# ESP-WROOM02-Breakout_v11.net
KiCad netlist of a schematic drawn in EAGLE
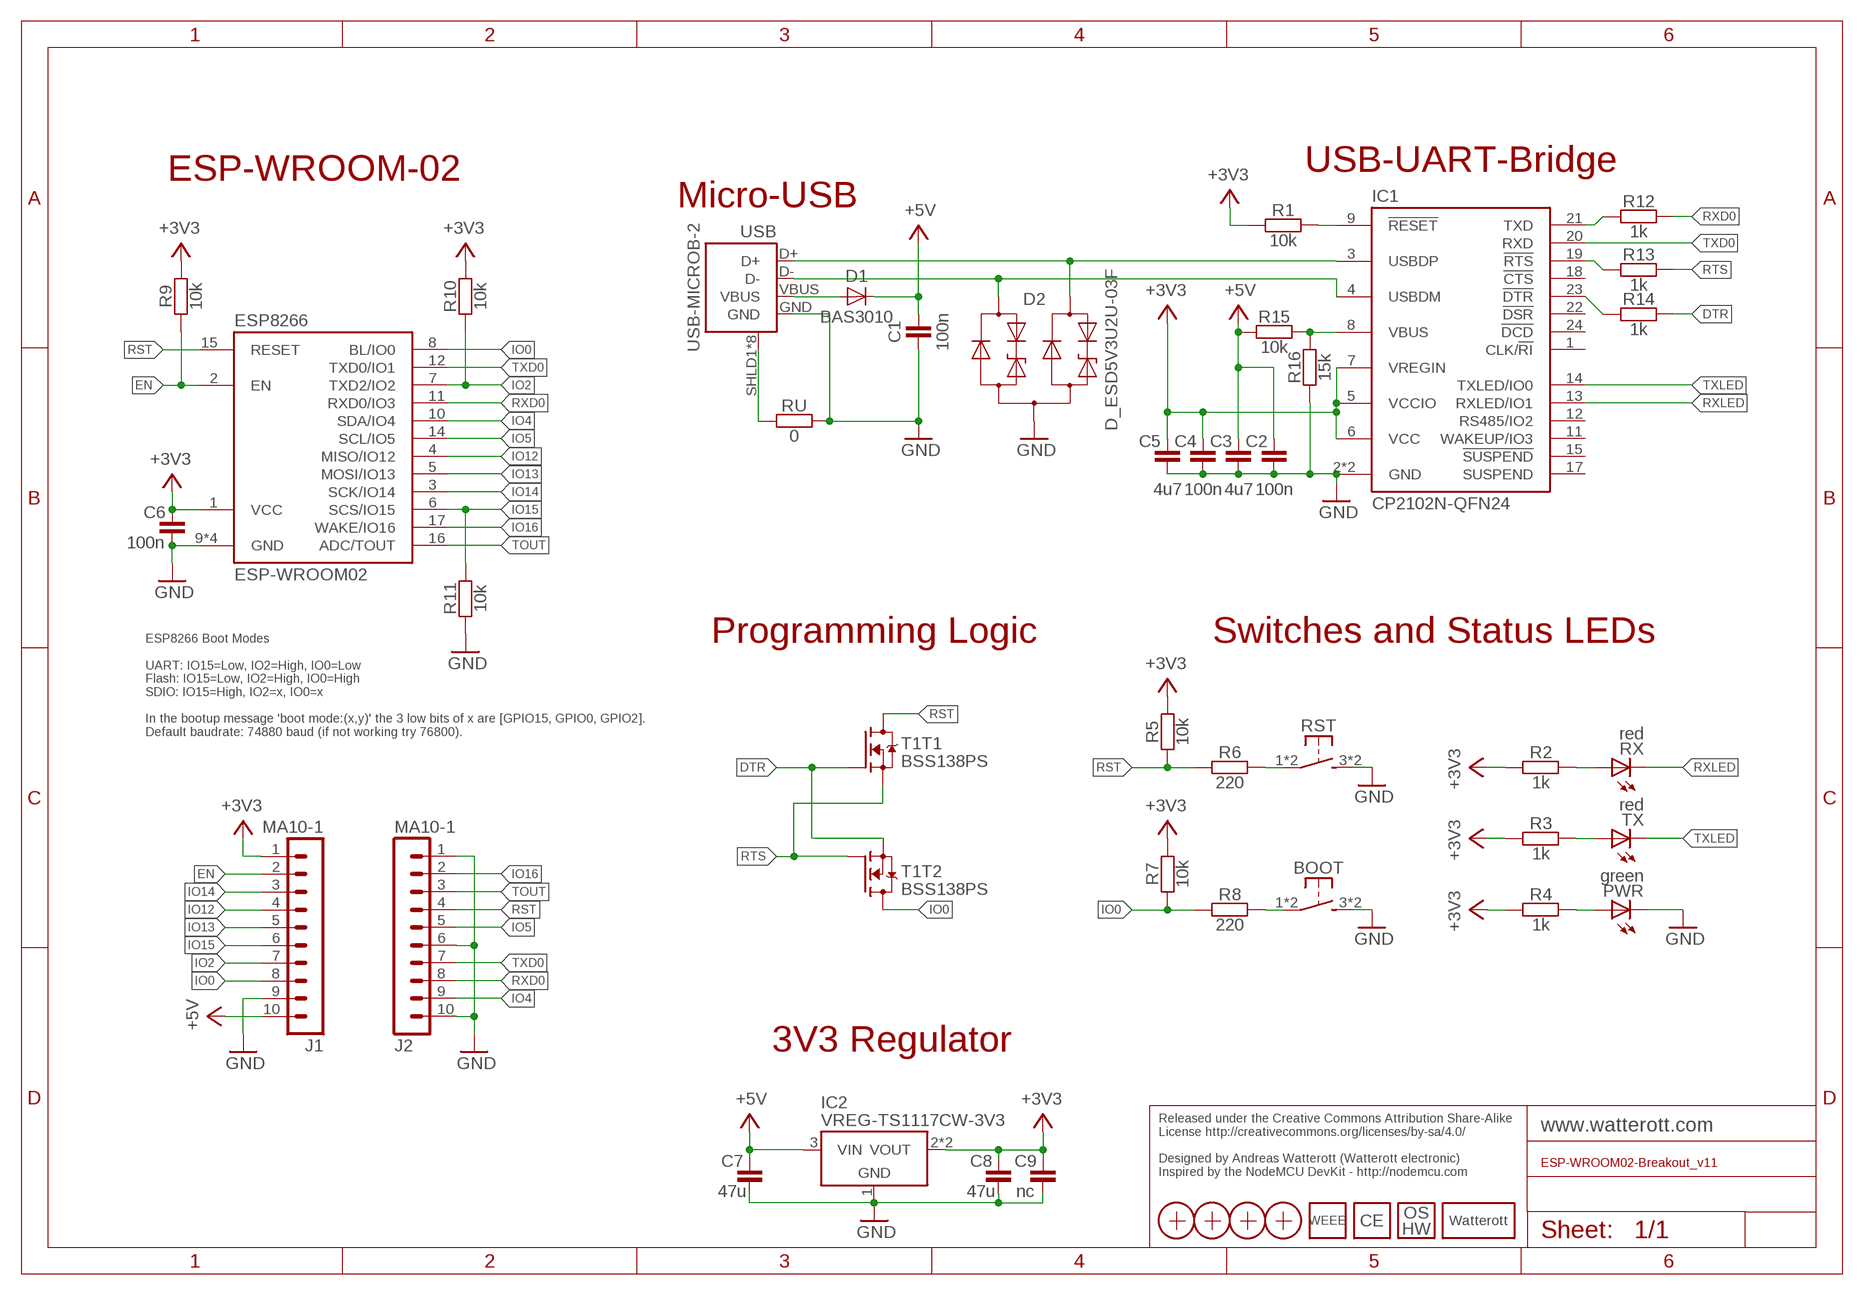
[diagram p0: schematic, sheet 1]

(export (version "E")
  (design (tool "Eeschema 10.0.6"))
  (components
    (comp (ref "BOOT")
      (value "SW-TACTILE-PTS840P")
      (footprint "eagle-import:PTS840P")
      (libsource (lib "eagle-import") (part "SW-TACTILE-PTS840P"))
    )
    (comp (ref "C1")
      (value "100n")
      (footprint "eagle-import:C0402")
      (libsource (lib "eagle-import") (part "CAPACITOR-0402"))
    )
    (comp (ref "C2")
      (value "100n")
      (footprint "eagle-import:C0402")
      (libsource (lib "eagle-import") (part "CAPACITOR-0402"))
    )
    (comp (ref "C3")
      (value "4u7")
      (footprint "eagle-import:C0603")
      (libsource (lib "eagle-import") (part "CAPACITOR-0603"))
    )
    (comp (ref "C4")
      (value "100n")
      (footprint "eagle-import:C0402")
      (libsource (lib "eagle-import") (part "CAPACITOR-0402"))
    )
    (comp (ref "C5")
      (value "4u7")
      (footprint "eagle-import:C0603")
      (libsource (lib "eagle-import") (part "CAPACITOR-0603"))
    )
    (comp (ref "C6")
      (value "100n")
      (footprint "eagle-import:C0402")
      (libsource (lib "eagle-import") (part "CAPACITOR-0402"))
    )
    (comp (ref "C7")
      (value "47u")
      (footprint "eagle-import:C1206")
      (libsource (lib "eagle-import") (part "CAPACITOR-1206"))
    )
    (comp (ref "C8")
      (value "47u")
      (footprint "eagle-import:C1206")
      (libsource (lib "eagle-import") (part "CAPACITOR-1206"))
    )
    (comp (ref "C9")
      (value "nc")
      (footprint "eagle-import:C1206")
      (libsource (lib "eagle-import") (part "CAPACITOR-1206"))
    )
    (comp (ref "D1")
      (value "BAS3010")
      (footprint "eagle-import:SOD323")
      (libsource (lib "eagle-import") (part "DIODE-SOD323"))
    )
    (comp (ref "D2")
      (value "D_ESD5V3U2U-03F")
      (footprint "eagle-import:SOT723")
      (libsource (lib "eagle-import") (part "D_ESD5V3U2U-03F"))
    )
    (comp (ref "ESP8266")
      (value "ESP-WROOM02")
      (footprint "eagle-import:ESP-WROOM02")
      (libsource (lib "eagle-import") (part "ESP-WROOM02"))
    )
    (comp (ref "IC1")
      (value "CP2102N-QFN24")
      (footprint "eagle-import:QFN24-PAD")
      (libsource (lib "eagle-import") (part "CP2102N-QFN24"))
    )
    (comp (ref "IC2")
      (value "VREG-TS1117CW-3V3")
      (footprint "eagle-import:SOT223")
      (libsource (lib "eagle-import") (part "VREG-TS1117CW-3V3"))
    )
    (comp (ref "J1")
      (value "MA10-1")
      (footprint "eagle-import:MA10-1")
      (libsource (lib "eagle-import") (part "MA10-1"))
    )
    (comp (ref "J2")
      (value "MA10-1")
      (footprint "eagle-import:MA10-1")
      (libsource (lib "eagle-import") (part "MA10-1"))
    )
    (comp (ref "LOGO1")
      (value "LOGO_SPARK-4")
      (footprint "eagle-import:SPARK_4MM")
      (libsource (lib "eagle-import") (part "LOGO_SPARK-4"))
    )
    (comp (ref "LOGO2")
      (value "LOGO_OSHW-2")
      (footprint "eagle-import:OSHW_2MM")
      (libsource (lib "eagle-import") (part "LOGO_OSHW-2"))
    )
    (comp (ref "LOGO3")
      (value "LOGO_WEEE-4")
      (footprint "eagle-import:WEEE_4MM")
      (libsource (lib "eagle-import") (part "LOGO_WEEE-4"))
    )
    (comp (ref "LOGO4")
      (value "LOGO_CE-2")
      (footprint "eagle-import:CE_2MM")
      (libsource (lib "eagle-import") (part "LOGO_CE-2"))
    )
    (comp (ref "PWR")
      (value "green")
      (footprint "eagle-import:C0603")
      (libsource (lib "eagle-import") (part "LED-0603"))
    )
    (comp (ref "R1")
      (value "10k")
      (footprint "eagle-import:C0402")
      (libsource (lib "eagle-import") (part "RESISTOR-0402"))
    )
    (comp (ref "R2")
      (value "1k")
      (footprint "eagle-import:C0402")
      (libsource (lib "eagle-import") (part "RESISTOR-0402"))
    )
    (comp (ref "R3")
      (value "1k")
      (footprint "eagle-import:C0402")
      (libsource (lib "eagle-import") (part "RESISTOR-0402"))
    )
    (comp (ref "R4")
      (value "1k")
      (footprint "eagle-import:C0402")
      (libsource (lib "eagle-import") (part "RESISTOR-0402"))
    )
    (comp (ref "R5")
      (value "10k")
      (footprint "eagle-import:C0402")
      (libsource (lib "eagle-import") (part "RESISTOR-0402"))
    )
    (comp (ref "R6")
      (value "220")
      (footprint "eagle-import:C0402")
      (libsource (lib "eagle-import") (part "RESISTOR-0402"))
    )
    (comp (ref "R7")
      (value "10k")
      (footprint "eagle-import:C0402")
      (libsource (lib "eagle-import") (part "RESISTOR-0402"))
    )
    (comp (ref "R8")
      (value "220")
      (footprint "eagle-import:C0402")
      (libsource (lib "eagle-import") (part "RESISTOR-0402"))
    )
    (comp (ref "R9")
      (value "10k")
      (footprint "eagle-import:C0402")
      (libsource (lib "eagle-import") (part "RESISTOR-0402"))
    )
    (comp (ref "R10")
      (value "10k")
      (footprint "eagle-import:C0402")
      (libsource (lib "eagle-import") (part "RESISTOR-0402"))
    )
    (comp (ref "R11")
      (value "10k")
      (footprint "eagle-import:C0402")
      (libsource (lib "eagle-import") (part "RESISTOR-0402"))
    )
    (comp (ref "R12")
      (value "1k")
      (footprint "eagle-import:C0402")
      (libsource (lib "eagle-import") (part "RESISTOR-0402"))
    )
    (comp (ref "R13")
      (value "1k")
      (footprint "eagle-import:C0402")
      (libsource (lib "eagle-import") (part "RESISTOR-0402"))
    )
    (comp (ref "R14")
      (value "1k")
      (footprint "eagle-import:C0402")
      (libsource (lib "eagle-import") (part "RESISTOR-0402"))
    )
    (comp (ref "R15")
      (value "10k")
      (footprint "eagle-import:C0402")
      (libsource (lib "eagle-import") (part "RESISTOR-0402"))
    )
    (comp (ref "R16")
      (value "15k")
      (footprint "eagle-import:C0402")
      (libsource (lib "eagle-import") (part "RESISTOR-0402"))
    )
    (comp (ref "RST")
      (value "SW-TACTILE-PTS840P")
      (footprint "eagle-import:PTS840P")
      (libsource (lib "eagle-import") (part "SW-TACTILE-PTS840P"))
    )
    (comp (ref "RU")
      (value "0")
      (footprint "eagle-import:C0402")
      (libsource (lib "eagle-import") (part "RESISTOR-0402"))
    )
    (comp (ref "RX")
      (value "red")
      (footprint "eagle-import:C0603")
      (libsource (lib "eagle-import") (part "LED-0603"))
    )
    (comp (ref "T1")
      (value "BSS138PS")
      (footprint "eagle-import:SOT363")
      (libsource (lib "eagle-import") (part "BSS138PS"))
    )
    (comp (ref "TX")
      (value "red")
      (footprint "eagle-import:C0603")
      (libsource (lib "eagle-import") (part "LED-0603"))
    )
    (comp (ref "USB")
      (value "USB-MICROB-2")
      (footprint "eagle-import:USB-MICROB-10118194")
      (libsource (lib "eagle-import") (part "USB-MICROB-2"))
    )
    (comp (ref "X1")
      (value "PASSER-07")
      (footprint "eagle-import:PASSER_07MM")
      (libsource (lib "eagle-import") (part "PASSER-07"))
    )
    (comp (ref "X2")
      (value "PASSER-07")
      (footprint "eagle-import:PASSER_07MM")
      (libsource (lib "eagle-import") (part "PASSER-07"))
    )
    (comp (ref "X3")
      (value "PASSER-07")
      (footprint "eagle-import:PASSER_07MM")
      (libsource (lib "eagle-import") (part "PASSER-07"))
    )
    (comp (ref "X4")
      (value "PASSER-07")
      (footprint "eagle-import:PASSER_07MM")
      (libsource (lib "eagle-import") (part "PASSER-07"))
    )
  )
  (nets
    (net (code "1") (name "+3V3") (class "Default")
      (node (ref "C4") (pin "2") (pinfunction "2_2") (pintype "passive"))
      (node (ref "C5") (pin "2") (pinfunction "2_2") (pintype "passive"))
      (node (ref "C6") (pin "2") (pinfunction "2_2") (pintype "passive"))
      (node (ref "C8") (pin "2") (pinfunction "2_2") (pintype "passive"))
      (node (ref "C9") (pin "2") (pinfunction "2_2") (pintype "passive"))
      (node (ref "ESP8266") (pin "1") (pinfunction "VCC_1") (pintype "power_in"))
      (node (ref "IC1") (pin "5") (pinfunction "VCCIO_5") (pintype "power_in"))
      (node (ref "IC1") (pin "6") (pinfunction "VCC_6") (pintype "power_in"))
      (node (ref "IC1") (pin "7") (pinfunction "VREGIN_7") (pintype "power_in"))
      (node (ref "IC2") (pin "2") (pinfunction "VOUT_2") (pintype "power_in"))
      (node (ref "IC2") (pin "4") (pinfunction "VOUT_4") (pintype "power_in"))
      (node (ref "J1") (pin "1") (pinfunction "1_1") (pintype "passive"))
      (node (ref "R1") (pin "1") (pinfunction "1_1") (pintype "passive"))
      (node (ref "R10") (pin "2") (pinfunction "2_2") (pintype "passive"))
      (node (ref "R2") (pin "1") (pinfunction "1_1") (pintype "passive"))
      (node (ref "R3") (pin "1") (pinfunction "1_1") (pintype "passive"))
      (node (ref "R4") (pin "1") (pinfunction "1_1") (pintype "passive"))
      (node (ref "R5") (pin "2") (pinfunction "2_2") (pintype "passive"))
      (node (ref "R7") (pin "2") (pinfunction "2_2") (pintype "passive"))
      (node (ref "R9") (pin "2") (pinfunction "2_2") (pintype "passive"))
    )
    (net (code "2") (name "+5V") (class "Default")
      (node (ref "C1") (pin "2") (pinfunction "2_2") (pintype "passive"))
      (node (ref "C2") (pin "2") (pinfunction "2_2") (pintype "passive"))
      (node (ref "C3") (pin "2") (pinfunction "2_2") (pintype "passive"))
      (node (ref "C7") (pin "2") (pinfunction "2_2") (pintype "passive"))
      (node (ref "D1") (pin "C") (pinfunction "C_C") (pintype "passive"))
      (node (ref "IC2") (pin "3") (pinfunction "VIN_3") (pintype "power_in"))
      (node (ref "J1") (pin "10") (pinfunction "10_10") (pintype "passive"))
      (node (ref "R15") (pin "1") (pinfunction "1_1") (pintype "passive"))
    )
    (net (code "3") (name "DTR") (class "Default")
      (node (ref "R14") (pin "2") (pinfunction "2_2") (pintype "passive"))
      (node (ref "T1") (pin "2") (pinfunction "G_2") (pintype "passive"))
      (node (ref "T1") (pin "4") (pinfunction "S_4") (pintype "passive"))
    )
    (net (code "4") (name "EN") (class "Default")
      (node (ref "ESP8266") (pin "2") (pinfunction "EN_2") (pintype "bidirectional"))
      (node (ref "J1") (pin "2") (pinfunction "2_2") (pintype "passive"))
      (node (ref "R9") (pin "1") (pinfunction "1_1") (pintype "passive"))
    )
    (net (code "5") (name "GND") (class "Default")
      (node (ref "BOOT") (pin "3") (pinfunction "S1_3") (pintype "passive"))
      (node (ref "BOOT") (pin "4") (pinfunction "S1_4") (pintype "passive"))
      (node (ref "C1") (pin "1") (pinfunction "1_1") (pintype "passive"))
      (node (ref "C2") (pin "1") (pinfunction "1_1") (pintype "passive"))
      (node (ref "C3") (pin "1") (pinfunction "1_1") (pintype "passive"))
      (node (ref "C4") (pin "1") (pinfunction "1_1") (pintype "passive"))
      (node (ref "C5") (pin "1") (pinfunction "1_1") (pintype "passive"))
      (node (ref "C6") (pin "1") (pinfunction "1_1") (pintype "passive"))
      (node (ref "C7") (pin "1") (pinfunction "1_1") (pintype "passive"))
      (node (ref "C8") (pin "1") (pinfunction "1_1") (pintype "passive"))
      (node (ref "C9") (pin "1") (pinfunction "1_1") (pintype "passive"))
      (node (ref "D2") (pin "3") (pinfunction "A_3") (pintype "passive"))
      (node (ref "ESP8266") (pin "13") (pinfunction "GND_13") (pintype "power_in"))
      (node (ref "ESP8266") (pin "18") (pinfunction "GND_18") (pintype "power_in"))
      (node (ref "ESP8266") (pin "9") (pinfunction "GND_9") (pintype "power_in"))
      (node (ref "ESP8266") (pin "TP") (pinfunction "GND_TP") (pintype "power_in"))
      (node (ref "IC1") (pin "2") (pinfunction "GND_2") (pintype "power_in"))
      (node (ref "IC1") (pin "TP") (pinfunction "GND_TP") (pintype "power_in"))
      (node (ref "IC2") (pin "1") (pinfunction "GND_1") (pintype "power_in"))
      (node (ref "J1") (pin "9") (pinfunction "9_9") (pintype "passive"))
      (node (ref "J2") (pin "1") (pinfunction "1_1") (pintype "passive"))
      (node (ref "J2") (pin "10") (pinfunction "10_10") (pintype "passive"))
      (node (ref "J2") (pin "6") (pinfunction "6_6") (pintype "passive"))
      (node (ref "PWR") (pin "C") (pinfunction "C_C") (pintype "passive"))
      (node (ref "R11") (pin "1") (pinfunction "1_1") (pintype "passive"))
      (node (ref "R16") (pin "1") (pinfunction "1_1") (pintype "passive"))
      (node (ref "RST") (pin "3") (pinfunction "S1_3") (pintype "passive"))
      (node (ref "RST") (pin "4") (pinfunction "S1_4") (pintype "passive"))
      (node (ref "RU") (pin "2") (pinfunction "2_2") (pintype "passive"))
      (node (ref "USB") (pin "GND") (pinfunction "GND_GND") (pintype "power_in"))
    )
    (net (code "6") (name "IO0") (class "Default")
      (node (ref "ESP8266") (pin "8") (pinfunction "BL/IO0_8") (pintype "bidirectional"))
      (node (ref "J1") (pin "8") (pinfunction "8_8") (pintype "passive"))
      (node (ref "R7") (pin "1") (pinfunction "1_1") (pintype "passive"))
      (node (ref "R8") (pin "1") (pinfunction "1_1") (pintype "passive"))
      (node (ref "T1") (pin "3") (pinfunction "D_3") (pintype "passive"))
    )
    (net (code "7") (name "IO2") (class "Default")
      (node (ref "ESP8266") (pin "7") (pinfunction "TXD2/IO2_7") (pintype "bidirectional"))
      (node (ref "J1") (pin "7") (pinfunction "7_7") (pintype "passive"))
      (node (ref "R10") (pin "1") (pinfunction "1_1") (pintype "passive"))
    )
    (net (code "8") (name "IO4") (class "Default")
      (node (ref "ESP8266") (pin "10") (pinfunction "SDA/IO4_10") (pintype "bidirectional"))
      (node (ref "J2") (pin "9") (pinfunction "9_9") (pintype "passive"))
    )
    (net (code "9") (name "IO5") (class "Default")
      (node (ref "ESP8266") (pin "14") (pinfunction "SCL/IO5_14") (pintype "bidirectional"))
      (node (ref "J2") (pin "5") (pinfunction "5_5") (pintype "passive"))
    )
    (net (code "10") (name "IO12") (class "Default")
      (node (ref "ESP8266") (pin "4") (pinfunction "MISO/IO12_4") (pintype "bidirectional"))
      (node (ref "J1") (pin "4") (pinfunction "4_4") (pintype "passive"))
    )
    (net (code "11") (name "IO13") (class "Default")
      (node (ref "ESP8266") (pin "5") (pinfunction "MOSI/IO13_5") (pintype "bidirectional"))
      (node (ref "J1") (pin "5") (pinfunction "5_5") (pintype "passive"))
    )
    (net (code "12") (name "IO14") (class "Default")
      (node (ref "ESP8266") (pin "3") (pinfunction "SCK/IO14_3") (pintype "bidirectional"))
      (node (ref "J1") (pin "3") (pinfunction "3_3") (pintype "passive"))
    )
    (net (code "13") (name "IO15") (class "Default")
      (node (ref "ESP8266") (pin "6") (pinfunction "SCS/IO15_6") (pintype "bidirectional"))
      (node (ref "J1") (pin "6") (pinfunction "6_6") (pintype "passive"))
      (node (ref "R11") (pin "2") (pinfunction "2_2") (pintype "passive"))
    )
    (net (code "14") (name "IO16") (class "Default")
      (node (ref "ESP8266") (pin "17") (pinfunction "WAKE/IO16_17") (pintype "bidirectional"))
      (node (ref "J2") (pin "2") (pinfunction "2_2") (pintype "passive"))
    )
    (net (code "15") (name "Net-(BOOT-P1-Pad1)") (class "Default")
      (node (ref "BOOT") (pin "1") (pinfunction "P1_1") (pintype "passive"))
      (node (ref "BOOT") (pin "2") (pinfunction "P1_2") (pintype "passive"))
      (node (ref "R8") (pin "2") (pinfunction "2_2") (pintype "passive"))
    )
    (net (code "16") (name "Net-(D1-PadA)") (class "Default")
      (node (ref "D1") (pin "A") (pinfunction "A_A") (pintype "passive"))
      (node (ref "USB") (pin "VBUS") (pinfunction "VBUS_VBUS") (pintype "power_in"))
    )
    (net (code "17") (name "Net-(D2-C1)") (class "Default")
      (node (ref "D2") (pin "1") (pinfunction "C1_1") (pintype "passive"))
      (node (ref "IC1") (pin "4") (pinfunction "USBDM_4") (pintype "bidirectional"))
      (node (ref "USB") (pin "D-") (pinfunction "D-_D-") (pintype "bidirectional"))
    )
    (net (code "18") (name "Net-(D2-C2)") (class "Default")
      (node (ref "D2") (pin "2") (pinfunction "C2_2") (pintype "passive"))
      (node (ref "IC1") (pin "3") (pinfunction "USBDP_3") (pintype "bidirectional"))
      (node (ref "USB") (pin "D+") (pinfunction "D+_D+") (pintype "bidirectional"))
    )
    (net (code "19") (name "Net-(IC1-TXD)") (class "Default")
      (node (ref "IC1") (pin "21") (pinfunction "TXD_21") (pintype "bidirectional"))
      (node (ref "R12") (pin "1") (pinfunction "1_1") (pintype "passive"))
    )
    (net (code "20") (name "Net-(IC1-VBUS)") (class "Default")
      (node (ref "IC1") (pin "8") (pinfunction "VBUS_8") (pintype "power_in"))
      (node (ref "R15") (pin "2") (pinfunction "2_2") (pintype "passive"))
      (node (ref "R16") (pin "2") (pinfunction "2_2") (pintype "passive"))
    )
    (net (code "21") (name "Net-(IC1-~{DTR})") (class "Default")
      (node (ref "IC1") (pin "23") (pinfunction "~{DTR}_23") (pintype "bidirectional"))
      (node (ref "R14") (pin "1") (pinfunction "1_1") (pintype "passive"))
    )
    (net (code "22") (name "Net-(IC1-~{RESET})") (class "Default")
      (node (ref "IC1") (pin "9") (pinfunction "~{RESET}_9") (pintype "bidirectional"))
      (node (ref "R1") (pin "2") (pinfunction "2_2") (pintype "passive"))
    )
    (net (code "23") (name "Net-(IC1-~{RTS})") (class "Default")
      (node (ref "IC1") (pin "19") (pinfunction "~{RTS}_19") (pintype "bidirectional"))
      (node (ref "R13") (pin "1") (pinfunction "1_1") (pintype "passive"))
    )
    (net (code "24") (name "Net-(PWR-PadA)") (class "Default")
      (node (ref "PWR") (pin "A") (pinfunction "A_A") (pintype "passive"))
      (node (ref "R4") (pin "2") (pinfunction "2_2") (pintype "passive"))
    )
    (net (code "25") (name "Net-(R2-Pad2)") (class "Default")
      (node (ref "R2") (pin "2") (pinfunction "2_2") (pintype "passive"))
      (node (ref "RX") (pin "A") (pinfunction "A_A") (pintype "passive"))
    )
    (net (code "26") (name "Net-(R3-Pad2)") (class "Default")
      (node (ref "R3") (pin "2") (pinfunction "2_2") (pintype "passive"))
      (node (ref "TX") (pin "A") (pinfunction "A_A") (pintype "passive"))
    )
    (net (code "27") (name "Net-(R6-Pad2)") (class "Default")
      (node (ref "R6") (pin "2") (pinfunction "2_2") (pintype "passive"))
      (node (ref "RST") (pin "1") (pinfunction "P1_1") (pintype "passive"))
      (node (ref "RST") (pin "2") (pinfunction "P1_2") (pintype "passive"))
    )
    (net (code "28") (name "Net-(RU-Pad1)") (class "Default")
      (node (ref "RU") (pin "1") (pinfunction "1_1") (pintype "passive"))
      (node (ref "USB") (pin "SHLD1") (pinfunction "SHIELD_SHLD1") (pintype "passive"))
      (node (ref "USB") (pin "SHLD2") (pinfunction "SHIELD_SHLD2") (pintype "passive"))
      (node (ref "USB") (pin "SHLD3") (pinfunction "SHIELD_SHLD3") (pintype "passive"))
      (node (ref "USB") (pin "SHLD4") (pinfunction "SHIELD_SHLD4") (pintype "passive"))
      (node (ref "USB") (pin "SHLD5") (pinfunction "SHIELD_SHLD5") (pintype "passive"))
      (node (ref "USB") (pin "SHLD6") (pinfunction "SHIELD_SHLD6") (pintype "passive"))
      (node (ref "USB") (pin "SHLD7") (pinfunction "SHIELD_SHLD7") (pintype "passive"))
      (node (ref "USB") (pin "SHLD8") (pinfunction "SHIELD_SHLD8") (pintype "passive"))
    )
    (net (code "29") (name "RST") (class "Default")
      (node (ref "ESP8266") (pin "15") (pinfunction "RESET_15") (pintype "bidirectional"))
      (node (ref "J2") (pin "4") (pinfunction "4_4") (pintype "passive"))
      (node (ref "R5") (pin "1") (pinfunction "1_1") (pintype "passive"))
      (node (ref "R6") (pin "1") (pinfunction "1_1") (pintype "passive"))
      (node (ref "T1") (pin "6") (pinfunction "D_6") (pintype "passive"))
    )
    (net (code "30") (name "RTS") (class "Default")
      (node (ref "R13") (pin "2") (pinfunction "2_2") (pintype "passive"))
      (node (ref "T1") (pin "1") (pinfunction "S_1") (pintype "passive"))
      (node (ref "T1") (pin "5") (pinfunction "G_5") (pintype "passive"))
    )
    (net (code "31") (name "RXD0") (class "Default")
      (node (ref "ESP8266") (pin "11") (pinfunction "RXD0/IO3_11") (pintype "bidirectional"))
      (node (ref "J2") (pin "8") (pinfunction "8_8") (pintype "passive"))
      (node (ref "R12") (pin "2") (pinfunction "2_2") (pintype "passive"))
    )
    (net (code "32") (name "RXLED") (class "Default")
      (node (ref "IC1") (pin "13") (pinfunction "RXLED/IO1_13") (pintype "bidirectional"))
      (node (ref "RX") (pin "C") (pinfunction "C_C") (pintype "passive"))
    )
    (net (code "33") (name "TOUT") (class "Default")
      (node (ref "ESP8266") (pin "16") (pinfunction "ADC/TOUT_16") (pintype "bidirectional"))
      (node (ref "J2") (pin "3") (pinfunction "3_3") (pintype "passive"))
    )
    (net (code "34") (name "TXD0") (class "Default")
      (node (ref "ESP8266") (pin "12") (pinfunction "TXD0/IO1_12") (pintype "bidirectional"))
      (node (ref "IC1") (pin "20") (pinfunction "RXD_20") (pintype "bidirectional"))
      (node (ref "J2") (pin "7") (pinfunction "7_7") (pintype "passive"))
    )
    (net (code "35") (name "TXLED") (class "Default")
      (node (ref "IC1") (pin "14") (pinfunction "TXLED/IO0_14") (pintype "bidirectional"))
      (node (ref "TX") (pin "C") (pinfunction "C_C") (pintype "passive"))
    )
    (net (code "36") (name "unconnected-(IC1-CLK{slash}~{RI}-Pad1)") (class "Default")
      (node (ref "IC1") (pin "1") (pinfunction "CLK/~{RI}_1") (pintype "bidirectional"))
    )
    (net (code "37") (name "unconnected-(IC1-RS485{slash}IO2-Pad12)") (class "Default")
      (node (ref "IC1") (pin "12") (pinfunction "RS485/IO2_12") (pintype "bidirectional"))
    )
    (net (code "38") (name "unconnected-(IC1-SUSPEND-Pad17)") (class "Default")
      (node (ref "IC1") (pin "17") (pinfunction "SUSPEND_17") (pintype "bidirectional"))
    )
    (net (code "39") (name "unconnected-(IC1-WAKEUP{slash}IO3-Pad11)") (class "Default")
      (node (ref "IC1") (pin "11") (pinfunction "WAKEUP/IO3_11") (pintype "bidirectional"))
    )
    (net (code "40") (name "unconnected-(IC1-~{CTS}-Pad18)") (class "Default")
      (node (ref "IC1") (pin "18") (pinfunction "~{CTS}_18") (pintype "bidirectional"))
    )
    (net (code "41") (name "unconnected-(IC1-~{DCD}-Pad24)") (class "Default")
      (node (ref "IC1") (pin "24") (pinfunction "~{DCD}_24") (pintype "bidirectional"))
    )
    (net (code "42") (name "unconnected-(IC1-~{DSR}-Pad22)") (class "Default")
      (node (ref "IC1") (pin "22") (pinfunction "~{DSR}_22") (pintype "bidirectional"))
    )
    (net (code "43") (name "unconnected-(IC1-~{SUSPEND}-Pad15)") (class "Default")
      (node (ref "IC1") (pin "15") (pinfunction "~{SUSPEND}_15") (pintype "bidirectional"))
    )
  )
)
